# RPi-Breadboard_Bplus_v10.net
KiCad netlist of a schematic drawn in EAGLE
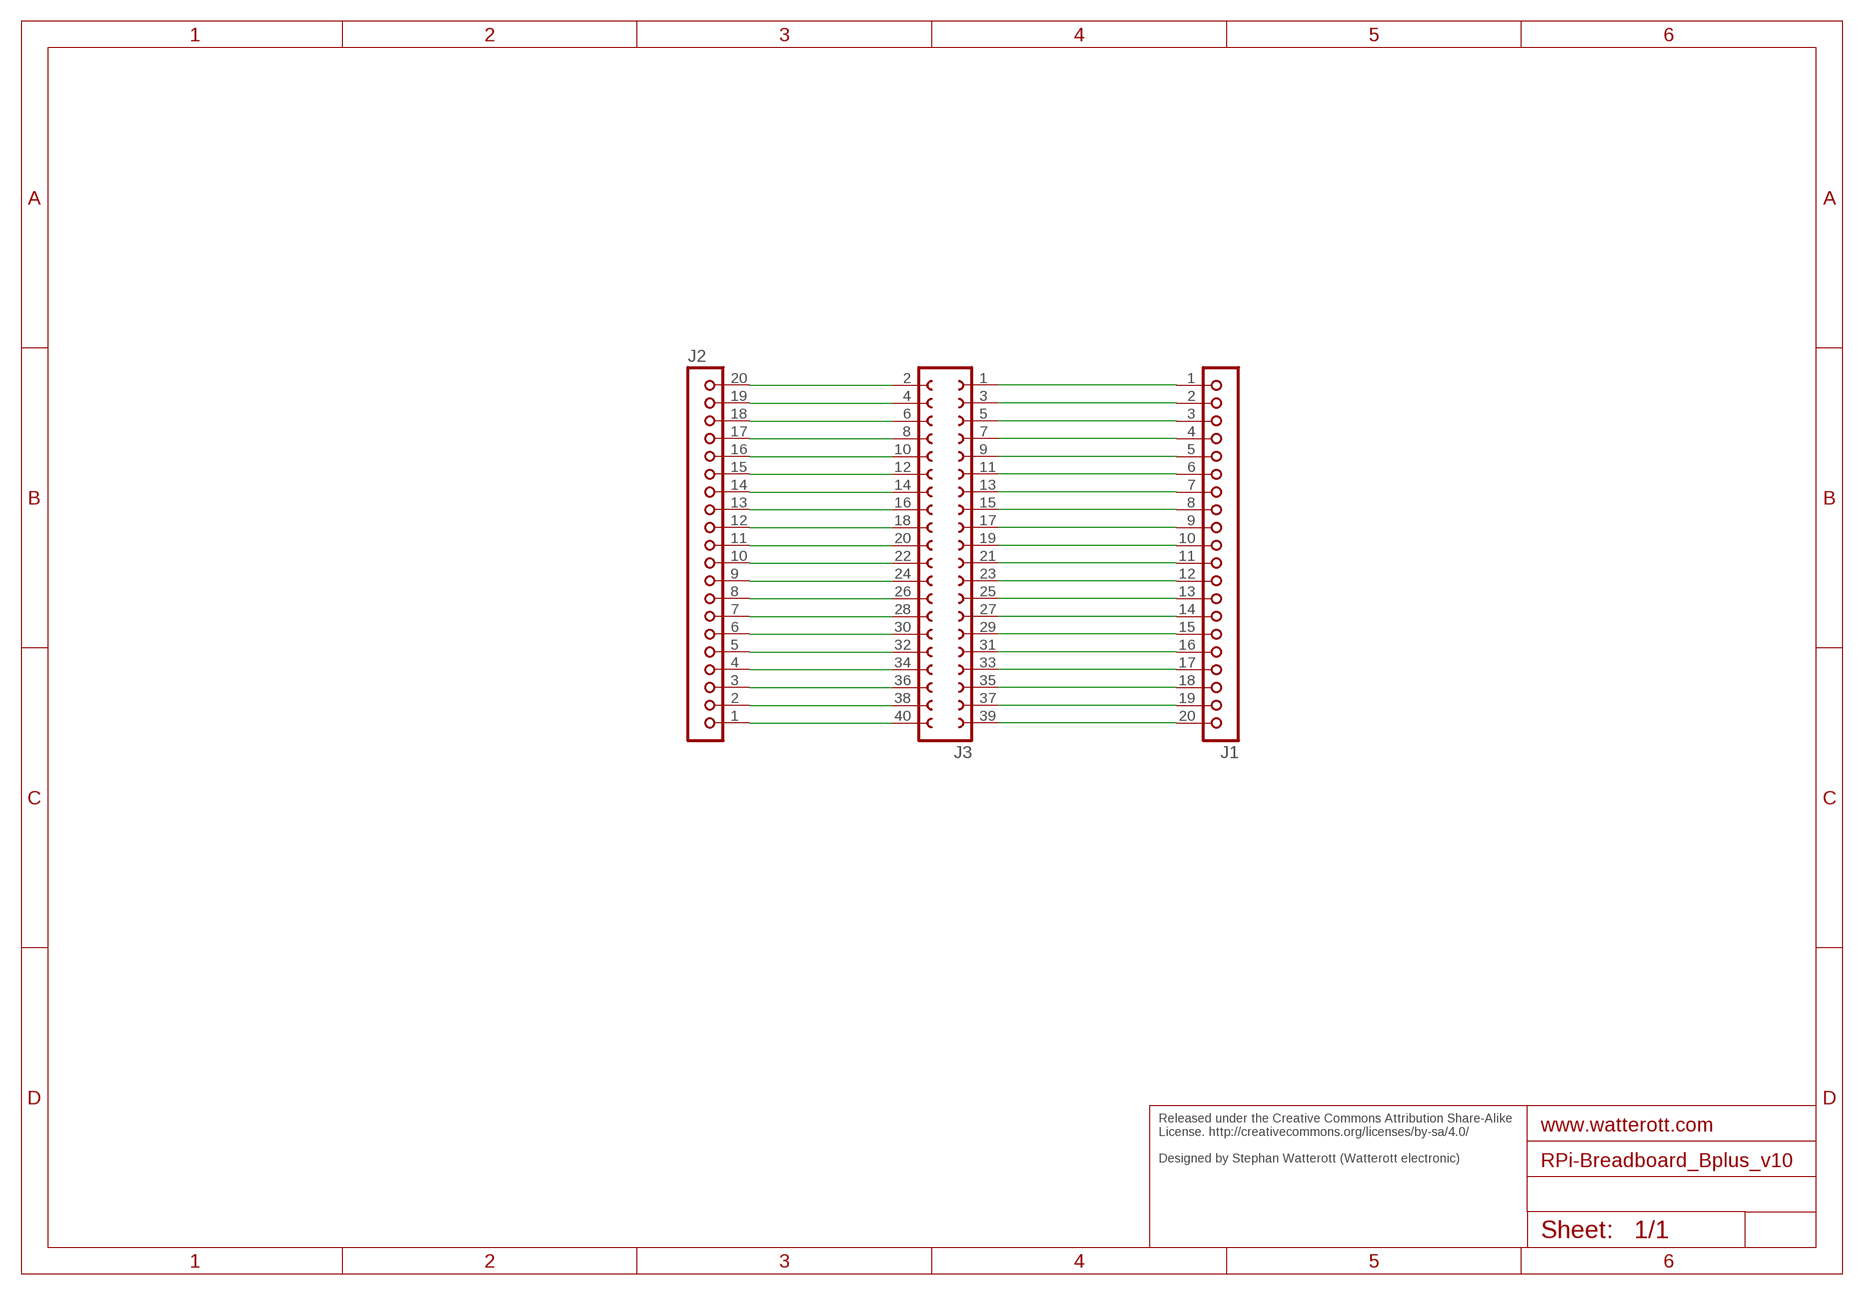
[diagram p0: schematic, sheet 1]

(export (version "E")
  (design (tool "Eeschema 10.0.6"))
  (components
    (comp (ref "J1")
      (value "JBK20")
      (footprint "eagle-import:JBK20")
      (libsource (lib "eagle-import") (part "JBK20"))
    )
    (comp (ref "J2")
      (value "JBK20")
      (footprint "eagle-import:JBK20")
      (libsource (lib "eagle-import") (part "JBK20"))
    )
    (comp (ref "J3")
      (value "FE20-2")
      (footprint "eagle-import:FE20-2")
      (libsource (lib "eagle-import") (part "FE20-2"))
    )
  )
  (nets
    (net (code "1") (name "/5V") (class "Default")
      (node (ref "J1") (pin "1") (pinfunction "1_1") (pintype "passive"))
      (node (ref "J1") (pin "2") (pinfunction "2_2") (pintype "passive"))
      (node (ref "J3") (pin "1") (pinfunction "1_1") (pintype "passive"))
      (node (ref "J3") (pin "3") (pinfunction "3_3") (pintype "passive"))
    )
    (net (code "2") (name "/GND") (class "Default")
      (node (ref "J1") (pin "10") (pinfunction "10_10") (pintype "passive"))
      (node (ref "J1") (pin "15") (pinfunction "15_15") (pintype "passive"))
      (node (ref "J1") (pin "17") (pinfunction "17_17") (pintype "passive"))
      (node (ref "J1") (pin "3") (pinfunction "3_3") (pintype "passive"))
      (node (ref "J1") (pin "7") (pinfunction "7_7") (pintype "passive"))
      (node (ref "J2") (pin "1") (pinfunction "1_1") (pintype "passive"))
      (node (ref "J2") (pin "16") (pinfunction "16_16") (pintype "passive"))
      (node (ref "J2") (pin "8") (pinfunction "8_8") (pintype "passive"))
      (node (ref "J3") (pin "10") (pinfunction "10_10") (pintype "passive"))
      (node (ref "J3") (pin "13") (pinfunction "13_13") (pintype "passive"))
      (node (ref "J3") (pin "19") (pinfunction "19_19") (pintype "passive"))
      (node (ref "J3") (pin "26") (pinfunction "26_26") (pintype "passive"))
      (node (ref "J3") (pin "29") (pinfunction "29_29") (pintype "passive"))
      (node (ref "J3") (pin "33") (pinfunction "33_33") (pintype "passive"))
      (node (ref "J3") (pin "40") (pinfunction "40_40") (pintype "passive"))
      (node (ref "J3") (pin "5") (pinfunction "5_5") (pintype "passive"))
    )
    (net (code "3") (name "Net-(J1-Pad4)") (class "Default")
      (node (ref "J1") (pin "4") (pinfunction "4_4") (pintype "passive"))
      (node (ref "J3") (pin "7") (pinfunction "7_7") (pintype "passive"))
    )
    (net (code "4") (name "Net-(J1-Pad5)") (class "Default")
      (node (ref "J1") (pin "5") (pinfunction "5_5") (pintype "passive"))
      (node (ref "J3") (pin "9") (pinfunction "9_9") (pintype "passive"))
    )
    (net (code "5") (name "Net-(J1-Pad6)") (class "Default")
      (node (ref "J1") (pin "6") (pinfunction "6_6") (pintype "passive"))
      (node (ref "J3") (pin "11") (pinfunction "11_11") (pintype "passive"))
    )
    (net (code "6") (name "Net-(J1-Pad8)") (class "Default")
      (node (ref "J1") (pin "8") (pinfunction "8_8") (pintype "passive"))
      (node (ref "J3") (pin "15") (pinfunction "15_15") (pintype "passive"))
    )
    (net (code "7") (name "Net-(J1-Pad9)") (class "Default")
      (node (ref "J1") (pin "9") (pinfunction "9_9") (pintype "passive"))
      (node (ref "J3") (pin "17") (pinfunction "17_17") (pintype "passive"))
    )
    (net (code "8") (name "Net-(J1-Pad11)") (class "Default")
      (node (ref "J1") (pin "11") (pinfunction "11_11") (pintype "passive"))
      (node (ref "J3") (pin "21") (pinfunction "21_21") (pintype "passive"))
    )
    (net (code "9") (name "Net-(J1-Pad12)") (class "Default")
      (node (ref "J1") (pin "12") (pinfunction "12_12") (pintype "passive"))
      (node (ref "J3") (pin "23") (pinfunction "23_23") (pintype "passive"))
    )
    (net (code "10") (name "Net-(J1-Pad13)") (class "Default")
      (node (ref "J1") (pin "13") (pinfunction "13_13") (pintype "passive"))
      (node (ref "J3") (pin "25") (pinfunction "25_25") (pintype "passive"))
    )
    (net (code "11") (name "Net-(J1-Pad14)") (class "Default")
      (node (ref "J1") (pin "14") (pinfunction "14_14") (pintype "passive"))
      (node (ref "J3") (pin "27") (pinfunction "27_27") (pintype "passive"))
    )
    (net (code "12") (name "Net-(J1-Pad16)") (class "Default")
      (node (ref "J1") (pin "16") (pinfunction "16_16") (pintype "passive"))
      (node (ref "J3") (pin "31") (pinfunction "31_31") (pintype "passive"))
    )
    (net (code "13") (name "Net-(J1-Pad18)") (class "Default")
      (node (ref "J1") (pin "18") (pinfunction "18_18") (pintype "passive"))
      (node (ref "J3") (pin "35") (pinfunction "35_35") (pintype "passive"))
    )
    (net (code "14") (name "Net-(J1-Pad19)") (class "Default")
      (node (ref "J1") (pin "19") (pinfunction "19_19") (pintype "passive"))
      (node (ref "J3") (pin "37") (pinfunction "37_37") (pintype "passive"))
    )
    (net (code "15") (name "Net-(J1-Pad20)") (class "Default")
      (node (ref "J1") (pin "20") (pinfunction "20_20") (pintype "passive"))
      (node (ref "J3") (pin "39") (pinfunction "39_39") (pintype "passive"))
    )
    (net (code "16") (name "Net-(J2-Pad2)") (class "Default")
      (node (ref "J2") (pin "2") (pinfunction "2_2") (pintype "passive"))
      (node (ref "J3") (pin "38") (pinfunction "38_38") (pintype "passive"))
    )
    (net (code "17") (name "Net-(J2-Pad3)") (class "Default")
      (node (ref "J2") (pin "3") (pinfunction "3_3") (pintype "passive"))
      (node (ref "J3") (pin "36") (pinfunction "36_36") (pintype "passive"))
    )
    (net (code "18") (name "Net-(J2-Pad4)") (class "Default")
      (node (ref "J2") (pin "4") (pinfunction "4_4") (pintype "passive"))
      (node (ref "J3") (pin "34") (pinfunction "34_34") (pintype "passive"))
    )
    (net (code "19") (name "Net-(J2-Pad5)") (class "Default")
      (node (ref "J2") (pin "5") (pinfunction "5_5") (pintype "passive"))
      (node (ref "J3") (pin "32") (pinfunction "32_32") (pintype "passive"))
    )
    (net (code "20") (name "Net-(J2-Pad6)") (class "Default")
      (node (ref "J2") (pin "6") (pinfunction "6_6") (pintype "passive"))
      (node (ref "J3") (pin "30") (pinfunction "30_30") (pintype "passive"))
    )
    (net (code "21") (name "Net-(J2-Pad7)") (class "Default")
      (node (ref "J2") (pin "7") (pinfunction "7_7") (pintype "passive"))
      (node (ref "J3") (pin "28") (pinfunction "28_28") (pintype "passive"))
    )
    (net (code "22") (name "Net-(J2-Pad9)") (class "Default")
      (node (ref "J2") (pin "9") (pinfunction "9_9") (pintype "passive"))
      (node (ref "J3") (pin "24") (pinfunction "24_24") (pintype "passive"))
    )
    (net (code "23") (name "Net-(J2-Pad10)") (class "Default")
      (node (ref "J2") (pin "10") (pinfunction "10_10") (pintype "passive"))
      (node (ref "J3") (pin "22") (pinfunction "22_22") (pintype "passive"))
    )
    (net (code "24") (name "Net-(J2-Pad11)") (class "Default")
      (node (ref "J2") (pin "11") (pinfunction "11_11") (pintype "passive"))
      (node (ref "J3") (pin "20") (pinfunction "20_20") (pintype "passive"))
    )
    (net (code "25") (name "Net-(J2-Pad12)") (class "Default")
      (node (ref "J2") (pin "12") (pinfunction "12_12") (pintype "passive"))
      (node (ref "J3") (pin "18") (pinfunction "18_18") (pintype "passive"))
    )
    (net (code "26") (name "Net-(J2-Pad13)") (class "Default")
      (node (ref "J2") (pin "13") (pinfunction "13_13") (pintype "passive"))
      (node (ref "J3") (pin "16") (pinfunction "16_16") (pintype "passive"))
    )
    (net (code "27") (name "Net-(J2-Pad14)") (class "Default")
      (node (ref "J2") (pin "14") (pinfunction "14_14") (pintype "passive"))
      (node (ref "J3") (pin "14") (pinfunction "14_14") (pintype "passive"))
    )
    (net (code "28") (name "Net-(J2-Pad15)") (class "Default")
      (node (ref "J2") (pin "15") (pinfunction "15_15") (pintype "passive"))
      (node (ref "J3") (pin "12") (pinfunction "12_12") (pintype "passive"))
    )
    (net (code "29") (name "Net-(J2-Pad17)") (class "Default")
      (node (ref "J2") (pin "17") (pinfunction "17_17") (pintype "passive"))
      (node (ref "J3") (pin "8") (pinfunction "8_8") (pintype "passive"))
    )
    (net (code "30") (name "Net-(J2-Pad18)") (class "Default")
      (node (ref "J2") (pin "18") (pinfunction "18_18") (pintype "passive"))
      (node (ref "J3") (pin "6") (pinfunction "6_6") (pintype "passive"))
    )
    (net (code "31") (name "Net-(J2-Pad19)") (class "Default")
      (node (ref "J2") (pin "19") (pinfunction "19_19") (pintype "passive"))
      (node (ref "J3") (pin "4") (pinfunction "4_4") (pintype "passive"))
    )
    (net (code "32") (name "Net-(J2-Pad20)") (class "Default")
      (node (ref "J2") (pin "20") (pinfunction "20_20") (pintype "passive"))
      (node (ref "J3") (pin "2") (pinfunction "2_2") (pintype "passive"))
    )
  )
)
